# ESP12E.net
KiCad netlist of a schematic drawn in EAGLE
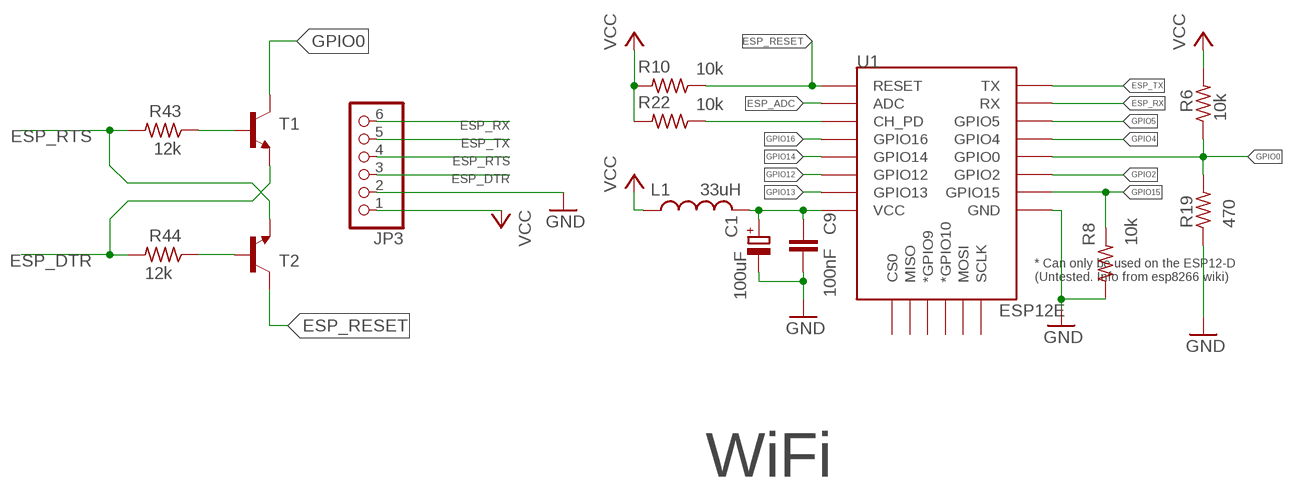
[diagram p0: schematic, sheet 1]

(export (version "E")
  (design (tool "Eeschema 10.0.6"))
  (components
    (comp (ref "C1")
      (value "100uF")
      (footprint "eagle-import:E2,5-6E")
      (libsource (lib "eagle-import") (part "CPOL-EUE2,5-6E"))
    )
    (comp (ref "C9")
      (value "100nF")
      (footprint "eagle-import:C050-024X044")
      (libsource (lib "eagle-import") (part "C-EU050-024X044"))
    )
    (comp (ref "JP3")
      (value "PINHD-1X6")
      (footprint "eagle-import:1X06")
      (libsource (lib "eagle-import") (part "PINHD-1X6"))
    )
    (comp (ref "L1")
      (value "33uH")
      (footprint "eagle-import:0207_10")
      (libsource (lib "eagle-import") (part "L-US0207/10"))
    )
    (comp (ref "R6")
      (value "10k")
      (footprint "eagle-import:0204_7")
      (libsource (lib "eagle-import") (part "R-US_0204/7"))
    )
    (comp (ref "R8")
      (value "10k")
      (footprint "eagle-import:0204_7")
      (libsource (lib "eagle-import") (part "R-US_0204/7"))
    )
    (comp (ref "R10")
      (value "10k")
      (footprint "eagle-import:0204_7")
      (libsource (lib "eagle-import") (part "R-US_0204/7"))
    )
    (comp (ref "R19")
      (value "470")
      (footprint "eagle-import:0204_7")
      (libsource (lib "eagle-import") (part "R-US_0204/7"))
    )
    (comp (ref "R22")
      (value "10k")
      (footprint "eagle-import:0204_7")
      (libsource (lib "eagle-import") (part "R-US_0204/7"))
    )
    (comp (ref "R43")
      (value "12k")
      (footprint "eagle-import:0204_7")
      (libsource (lib "eagle-import") (part "R-US_0204/7"))
    )
    (comp (ref "R44")
      (value "12k")
      (footprint "eagle-import:0204_7")
      (libsource (lib "eagle-import") (part "R-US_0204/7"))
    )
    (comp (ref "T1")
      (value "BC547-NPN-TO92-CBE")
      (footprint "eagle-import:TO92-CBE")
      (libsource (lib "eagle-import") (part "-NPN-TO92-CBEBC547"))
    )
    (comp (ref "T2")
      (value "BC547-NPN-TO92-CBE")
      (footprint "eagle-import:TO92-CBE")
      (libsource (lib "eagle-import") (part "-NPN-TO92-CBEBC547"))
    )
    (comp (ref "U1")
      (value "ESP12E")
      (footprint "eagle-import:ESP12E-SMD")
      (libsource (lib "eagle-import") (part "ESP12ESMD"))
    )
  )
  (nets
    (net (code "1") (name "/ESP_DTR") (class "Default")
      (node (ref "JP3") (pin "3") (pinfunction "3_3") (pintype "passive"))
      (node (ref "R44") (pin "2") (pinfunction "2_2") (pintype "passive"))
      (node (ref "T1") (pin "E") (pinfunction "E_E") (pintype "passive"))
    )
    (net (code "2") (name "/ESP_RTS") (class "Default")
      (node (ref "JP3") (pin "4") (pinfunction "4_4") (pintype "passive"))
      (node (ref "R43") (pin "2") (pinfunction "2_2") (pintype "passive"))
      (node (ref "T2") (pin "E") (pinfunction "E_E") (pintype "passive"))
    )
    (net (code "3") (name "ESP_ADC") (class "Default")
      (node (ref "U1") (pin "ADC") (pinfunction "ADC_ADC") (pintype "bidirectional"))
    )
    (net (code "4") (name "ESP_RESET") (class "Default")
      (node (ref "R10") (pin "1") (pinfunction "1_1") (pintype "passive"))
      (node (ref "T2") (pin "C") (pinfunction "C_C") (pintype "passive"))
      (node (ref "U1") (pin "RESET") (pinfunction "RESET_RESET") (pintype "bidirectional"))
    )
    (net (code "5") (name "ESP_RX") (class "Default")
      (node (ref "JP3") (pin "6") (pinfunction "6_6") (pintype "passive"))
      (node (ref "U1") (pin "RXD0") (pinfunction "RX_RXD0") (pintype "bidirectional"))
    )
    (net (code "6") (name "ESP_TX") (class "Default")
      (node (ref "JP3") (pin "5") (pinfunction "5_5") (pintype "passive"))
      (node (ref "U1") (pin "TXD0") (pinfunction "TX_TXD0") (pintype "bidirectional"))
    )
    (net (code "7") (name "GND") (class "Default")
      (node (ref "C1") (pin "-") (pinfunction "-_-") (pintype "passive"))
      (node (ref "C9") (pin "2") (pinfunction "2_2") (pintype "passive"))
      (node (ref "JP3") (pin "2") (pinfunction "2_2") (pintype "passive"))
      (node (ref "R19") (pin "1") (pinfunction "1_1") (pintype "passive"))
      (node (ref "R8") (pin "1") (pinfunction "1_1") (pintype "passive"))
      (node (ref "U1") (pin "GND") (pinfunction "GND_GND") (pintype "bidirectional"))
    )
    (net (code "8") (name "GPIO0") (class "Default")
      (node (ref "R19") (pin "2") (pinfunction "2_2") (pintype "passive"))
      (node (ref "R6") (pin "1") (pinfunction "1_1") (pintype "passive"))
      (node (ref "T1") (pin "C") (pinfunction "C_C") (pintype "passive"))
      (node (ref "U1") (pin "GPIO0") (pinfunction "GPIO0_GPIO0") (pintype "bidirectional"))
    )
    (net (code "9") (name "GPIO2") (class "Default")
      (node (ref "U1") (pin "GPIO2") (pinfunction "GPIO2_GPIO2") (pintype "bidirectional"))
    )
    (net (code "10") (name "GPIO4") (class "Default")
      (node (ref "U1") (pin "GPIO4") (pinfunction "GPIO4_GPIO4") (pintype "bidirectional"))
    )
    (net (code "11") (name "GPIO5") (class "Default")
      (node (ref "U1") (pin "GPIO5") (pinfunction "GPIO5_GPIO5") (pintype "bidirectional"))
    )
    (net (code "12") (name "GPIO12") (class "Default")
      (node (ref "U1") (pin "GPIO12") (pinfunction "GPIO12_GPIO12") (pintype "bidirectional"))
    )
    (net (code "13") (name "GPIO13") (class "Default")
      (node (ref "U1") (pin "GPIO13") (pinfunction "GPIO13_GPIO13") (pintype "bidirectional"))
    )
    (net (code "14") (name "GPIO14") (class "Default")
      (node (ref "U1") (pin "GPIO14") (pinfunction "GPIO14_GPIO14") (pintype "bidirectional"))
    )
    (net (code "15") (name "GPIO15") (class "Default")
      (node (ref "R8") (pin "2") (pinfunction "2_2") (pintype "passive"))
      (node (ref "U1") (pin "GPIO15") (pinfunction "GPIO15_GPIO15") (pintype "bidirectional"))
    )
    (net (code "16") (name "GPIO16") (class "Default")
      (node (ref "U1") (pin "GPIO16") (pinfunction "GPIO16_GPIO16") (pintype "bidirectional"))
    )
    (net (code "17") (name "Net-(C1-Pad+)") (class "Default")
      (node (ref "C1") (pin "+") (pinfunction "+_+") (pintype "passive"))
      (node (ref "C9") (pin "1") (pinfunction "1_1") (pintype "passive"))
      (node (ref "L1") (pin "2") (pinfunction "2_2") (pintype "passive"))
      (node (ref "U1") (pin "VCC") (pinfunction "VCC_VCC") (pintype "bidirectional"))
    )
    (net (code "18") (name "Net-(R22-Pad1)") (class "Default")
      (node (ref "R22") (pin "1") (pinfunction "1_1") (pintype "passive"))
      (node (ref "U1") (pin "CH_PD") (pinfunction "CH_PD_CH_PD") (pintype "bidirectional"))
    )
    (net (code "19") (name "Net-(R43-Pad1)") (class "Default")
      (node (ref "R43") (pin "1") (pinfunction "1_1") (pintype "passive"))
      (node (ref "T1") (pin "B") (pinfunction "B_B") (pintype "passive"))
    )
    (net (code "20") (name "Net-(R44-Pad1)") (class "Default")
      (node (ref "R44") (pin "1") (pinfunction "1_1") (pintype "passive"))
      (node (ref "T2") (pin "B") (pinfunction "B_B") (pintype "passive"))
    )
    (net (code "21") (name "VCC") (class "Default")
      (node (ref "JP3") (pin "1") (pinfunction "1_1") (pintype "passive"))
      (node (ref "L1") (pin "1") (pinfunction "1_1") (pintype "passive"))
      (node (ref "R10") (pin "2") (pinfunction "2_2") (pintype "passive"))
      (node (ref "R22") (pin "2") (pinfunction "2_2") (pintype "passive"))
      (node (ref "R6") (pin "2") (pinfunction "2_2") (pintype "passive"))
    )
    (net (code "22") (name "unconnected-(U1-*GPIO9-PadGPIO9)") (class "Default")
      (node (ref "U1") (pin "GPIO9") (pinfunction "*GPIO9_GPIO9") (pintype "bidirectional"))
    )
    (net (code "23") (name "unconnected-(U1-*GPIO10-PadGPIO10)") (class "Default")
      (node (ref "U1") (pin "GPIO10") (pinfunction "*GPIO10_GPIO10") (pintype "bidirectional"))
    )
    (net (code "24") (name "unconnected-(U1-PadCS0)") (class "Default")
      (node (ref "U1") (pin "CS0") (pinfunction "CS0_CS0") (pintype "bidirectional"))
    )
    (net (code "25") (name "unconnected-(U1-PadMISO)") (class "Default")
      (node (ref "U1") (pin "MISO") (pinfunction "MISO_MISO") (pintype "bidirectional"))
    )
    (net (code "26") (name "unconnected-(U1-PadMOSI)") (class "Default")
      (node (ref "U1") (pin "MOSI") (pinfunction "MOSI_MOSI") (pintype "bidirectional"))
    )
    (net (code "27") (name "unconnected-(U1-PadSCLK)") (class "Default")
      (node (ref "U1") (pin "SCLK") (pinfunction "SCLK_SCLK") (pintype "bidirectional"))
    )
  )
)
